# 2_RFD900x.net
KiCad netlist of a schematic drawn in Altium Designer
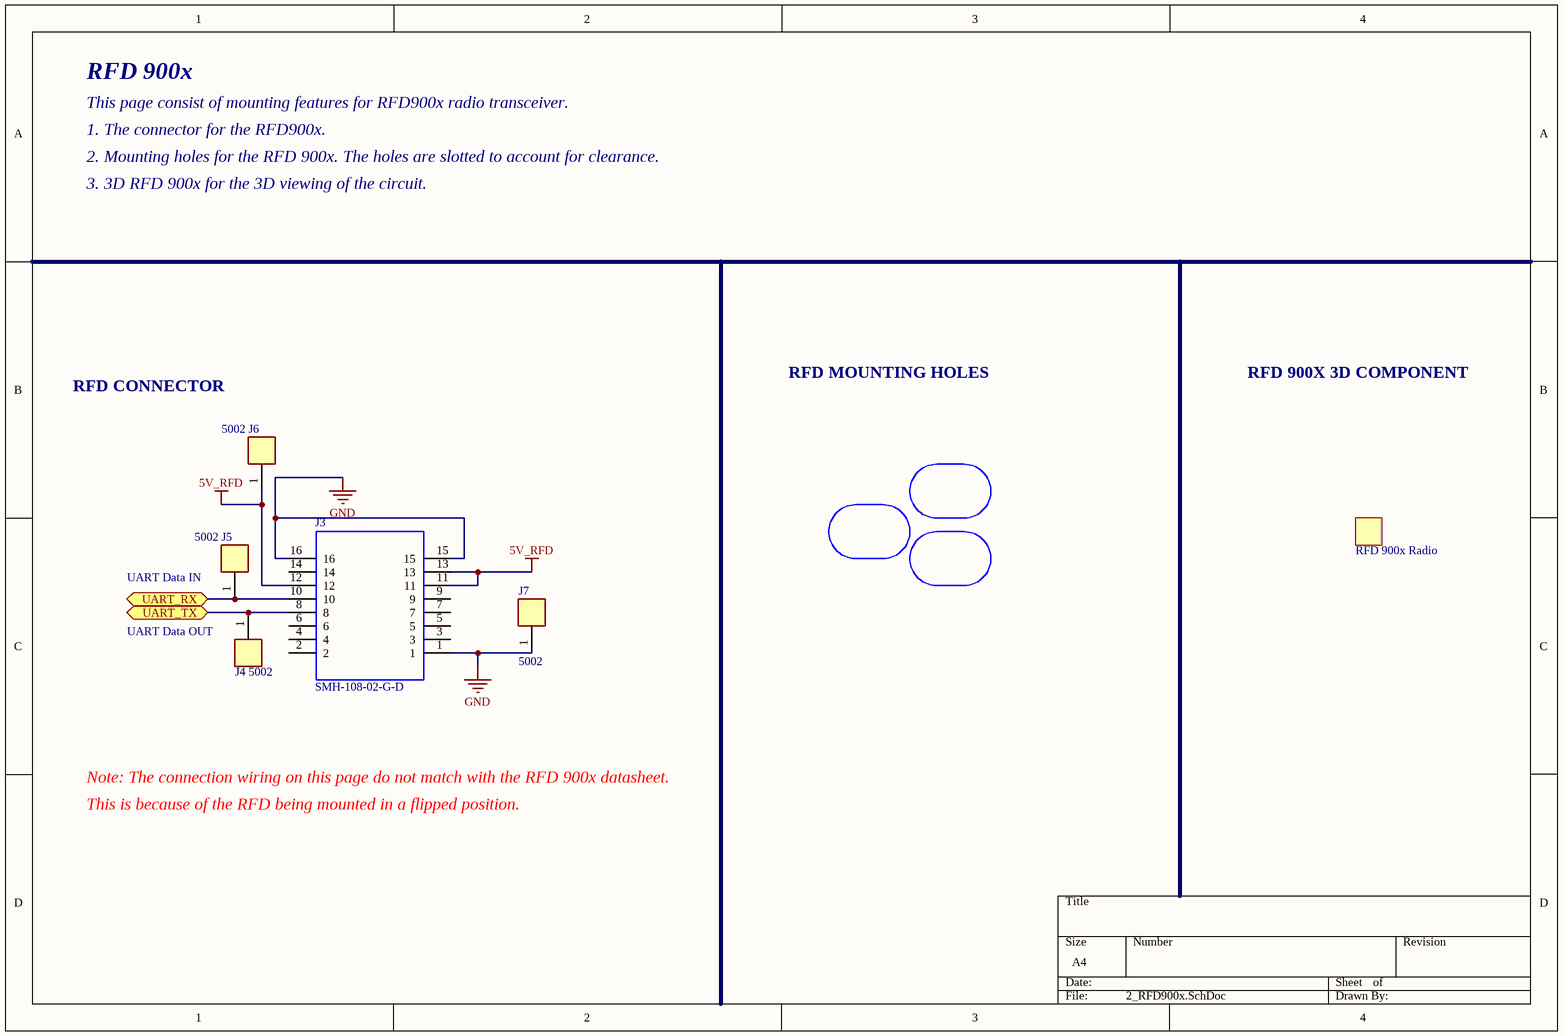
[diagram p0: 2_RFD900x.SchDoc]

(export (version "E")
  (design (tool "Eeschema 10.0.6"))
  (components
    (comp (ref "*")
      (value "RFD 900x Radio")
      (footprint "RFD900X")
      (libsource (lib "3D_Components") (part "RFD 900x Radio"))
    )
    (comp (ref "H5")
      (value "M3 not plated slotted")
      (footprint "M3 not plated - slotted")
      (description "M3 hole not plated slotted")
      (libsource (lib "Miscellaneous") (part "M3 not plated slotted"))
    )
    (comp (ref "H6")
      (value "M3 not plated slotted")
      (footprint "M3 not plated - slotted")
      (description "M3 hole not plated slotted")
      (libsource (lib "Miscellaneous") (part "M3 not plated slotted"))
    )
    (comp (ref "H7")
      (value "M3 not plated slotted")
      (footprint "M3 not plated - slotted")
      (description "M3 hole not plated slotted")
      (libsource (lib "Miscellaneous") (part "M3 not plated slotted"))
    )
    (comp (ref "J3")
      (value "SMH-108-02-G-D")
      (footprint "Connectors:SAMTEC_SMH-108-02-G-D")
      (description "SAMTEC 16POS 0.1\"pitch")
      (fields (field (name "PARTNUMBER") "SAM11816-ND"))
      (libsource (lib "Connectors") (part "SMH-108-02-G-D"))
    )
    (comp (ref "J4")
      (value "5002")
      (footprint "Miscellaneous:KEYSTONE_5002")
      (description "Test Point Ring Keystone")
      (fields (field (name "MANUFACTURER") "Keystone Electronics"))
      (libsource (lib "") (part "5002_1"))
    )
    (comp (ref "J5")
      (value "5002")
      (footprint "Miscellaneous:KEYSTONE_5002")
      (description "Test Point Ring Keystone")
      (fields (field (name "MANUFACTURER") "Keystone Electronics"))
      (libsource (lib "Miscellaneous") (part "5002"))
    )
    (comp (ref "J6")
      (value "5002")
      (footprint "Miscellaneous:KEYSTONE_5002")
      (description "Test Point Ring Keystone")
      (fields (field (name "MANUFACTURER") "Keystone Electronics"))
      (libsource (lib "Miscellaneous") (part "5002"))
    )
    (comp (ref "J7")
      (value "5002")
      (footprint "Miscellaneous:KEYSTONE_5002")
      (description "Test Point Ring Keystone")
      (fields (field (name "MANUFACTURER") "Keystone Electronics"))
      (libsource (lib "Miscellaneous") (part "5002"))
    )
  )
  (nets
    (net (code "1") (name "/UART_RX") (class "Default")
      (node (ref "J3") (pin "10") (pinfunction "10_10") (pintype "passive"))
      (node (ref "J5") (pin "1") (pintype "passive"))
    )
    (net (code "2") (name "/UART_TX") (class "Default")
      (node (ref "J3") (pin "8") (pinfunction "8_8") (pintype "passive"))
      (node (ref "J4") (pin "1") (pintype "passive"))
    )
    (net (code "3") (name "5V_RFD") (class "Default")
      (node (ref "J3") (pin "11") (pinfunction "11_11") (pintype "passive"))
      (node (ref "J3") (pin "12") (pinfunction "12_12") (pintype "passive"))
      (node (ref "J3") (pin "13") (pinfunction "13_13") (pintype "passive"))
      (node (ref "J6") (pin "1") (pintype "passive"))
    )
    (net (code "4") (name "GND") (class "Default")
      (node (ref "J3") (pin "1") (pinfunction "1_1") (pintype "passive"))
      (node (ref "J3") (pin "15") (pinfunction "15_15") (pintype "passive"))
      (node (ref "J3") (pin "16") (pinfunction "16_16") (pintype "passive"))
      (node (ref "J7") (pin "1") (pintype "passive"))
    )
    (net (code "5") (name "unconnected-(J3-Pad2)") (class "Default")
      (node (ref "J3") (pin "2") (pinfunction "2_2") (pintype "passive"))
    )
    (net (code "6") (name "unconnected-(J3-Pad3)") (class "Default")
      (node (ref "J3") (pin "3") (pinfunction "3_3") (pintype "passive"))
    )
    (net (code "7") (name "unconnected-(J3-Pad4)") (class "Default")
      (node (ref "J3") (pin "4") (pinfunction "4_4") (pintype "passive"))
    )
    (net (code "8") (name "unconnected-(J3-Pad5)") (class "Default")
      (node (ref "J3") (pin "5") (pinfunction "5_5") (pintype "passive"))
    )
    (net (code "9") (name "unconnected-(J3-Pad6)") (class "Default")
      (node (ref "J3") (pin "6") (pinfunction "6_6") (pintype "passive"))
    )
    (net (code "10") (name "unconnected-(J3-Pad7)") (class "Default")
      (node (ref "J3") (pin "7") (pinfunction "7_7") (pintype "passive"))
    )
    (net (code "11") (name "unconnected-(J3-Pad9)") (class "Default")
      (node (ref "J3") (pin "9") (pinfunction "9_9") (pintype "passive"))
    )
    (net (code "12") (name "unconnected-(J3-Pad14)") (class "Default")
      (node (ref "J3") (pin "14") (pinfunction "14_14") (pintype "passive"))
    )
  )
)
